# 9_FPGA_ADC_N.net
KiCad netlist of a schematic drawn in Altium Designer
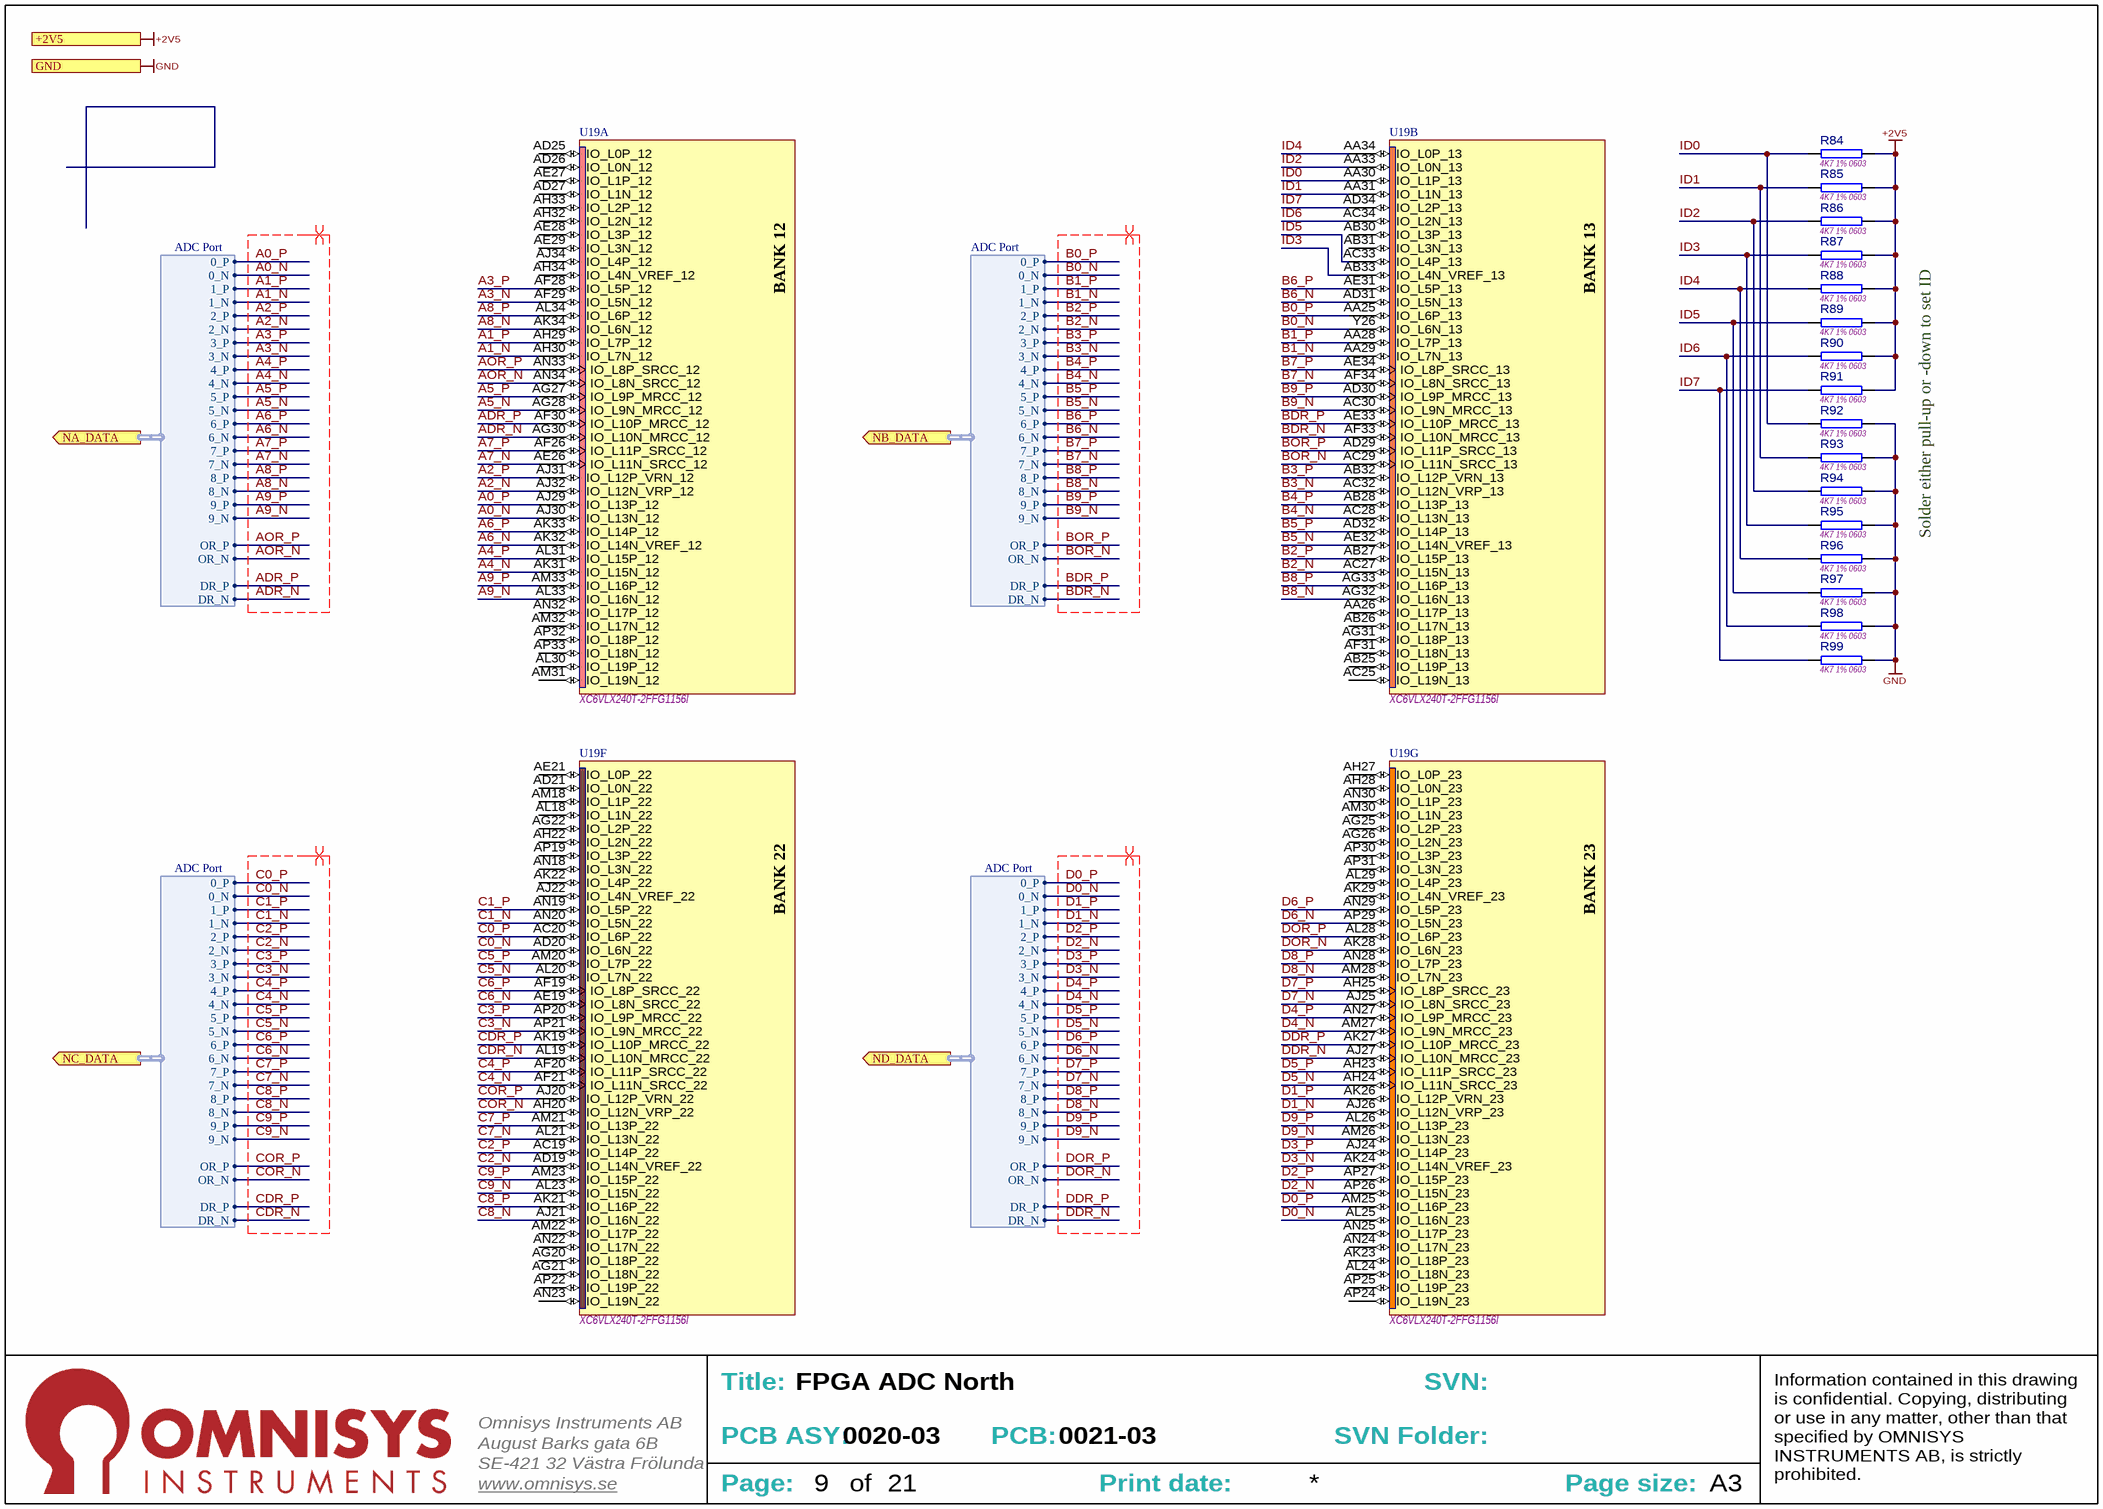
[diagram p0: [9] FPGA_ADC_N.SchDoc]

(export (version "E")
  (design (tool "Eeschema 10.0.6"))
  (components
    (comp (ref "R84")
      (value "4K7 1% 0603")
      (footprint "RESC1608N")
      (description "Thick film Chip Resistor, 0603/1608")
      (fields (field (name "POWER") "100mW") (field (name "TOLERANCE") "1%"))
      (libsource (lib "Omnisys Vault") (part "RES-2PIN"))
    )
    (comp (ref "R85")
      (value "4K7 1% 0603")
      (footprint "RESC1608N")
      (description "Thick film Chip Resistor, 0603/1608")
      (fields (field (name "POWER") "100mW") (field (name "TOLERANCE") "1%"))
      (libsource (lib "Omnisys Vault") (part "RES-2PIN"))
    )
    (comp (ref "R86")
      (value "4K7 1% 0603")
      (footprint "RESC1608N")
      (description "Thick film Chip Resistor, 0603/1608")
      (fields (field (name "POWER") "100mW") (field (name "TOLERANCE") "1%"))
      (libsource (lib "Omnisys Vault") (part "RES-2PIN"))
    )
    (comp (ref "R87")
      (value "4K7 1% 0603")
      (footprint "RESC1608N")
      (description "Thick film Chip Resistor, 0603/1608")
      (fields (field (name "POWER") "100mW") (field (name "TOLERANCE") "1%"))
      (libsource (lib "Omnisys Vault") (part "RES-2PIN"))
    )
    (comp (ref "R88")
      (value "4K7 1% 0603")
      (footprint "RESC1608N")
      (description "Thick film Chip Resistor, 0603/1608")
      (fields (field (name "POWER") "100mW") (field (name "TOLERANCE") "1%"))
      (libsource (lib "Omnisys Vault") (part "RES-2PIN"))
    )
    (comp (ref "R89")
      (value "4K7 1% 0603")
      (footprint "RESC1608N")
      (description "Thick film Chip Resistor, 0603/1608")
      (fields (field (name "POWER") "100mW") (field (name "TOLERANCE") "1%"))
      (libsource (lib "Omnisys Vault") (part "RES-2PIN"))
    )
    (comp (ref "R90")
      (value "4K7 1% 0603")
      (footprint "RESC1608N")
      (description "Thick film Chip Resistor, 0603/1608")
      (fields (field (name "POWER") "100mW") (field (name "TOLERANCE") "1%"))
      (libsource (lib "Omnisys Vault") (part "RES-2PIN"))
    )
    (comp (ref "R91")
      (value "4K7 1% 0603")
      (footprint "RESC1608N")
      (description "Thick film Chip Resistor, 0603/1608")
      (fields (field (name "POWER") "100mW") (field (name "TOLERANCE") "1%"))
      (libsource (lib "Omnisys Vault") (part "RES-2PIN"))
    )
    (comp (ref "R92")
      (value "4K7 1% 0603")
      (footprint "RESC1608N")
      (description "Thick film Chip Resistor, 0603/1608")
      (fields (field (name "POWER") "100mW") (field (name "TOLERANCE") "1%"))
      (libsource (lib "Omnisys Vault") (part "RES-2PIN"))
    )
    (comp (ref "R93")
      (value "4K7 1% 0603")
      (footprint "RESC1608N")
      (description "Thick film Chip Resistor, 0603/1608")
      (fields (field (name "POWER") "100mW") (field (name "TOLERANCE") "1%"))
      (libsource (lib "Omnisys Vault") (part "RES-2PIN"))
    )
    (comp (ref "R94")
      (value "4K7 1% 0603")
      (footprint "RESC1608N")
      (description "Thick film Chip Resistor, 0603/1608")
      (fields (field (name "POWER") "100mW") (field (name "TOLERANCE") "1%"))
      (libsource (lib "Omnisys Vault") (part "RES-2PIN"))
    )
    (comp (ref "R95")
      (value "4K7 1% 0603")
      (footprint "RESC1608N")
      (description "Thick film Chip Resistor, 0603/1608")
      (fields (field (name "POWER") "100mW") (field (name "TOLERANCE") "1%"))
      (libsource (lib "Omnisys Vault") (part "RES-2PIN"))
    )
    (comp (ref "R96")
      (value "4K7 1% 0603")
      (footprint "RESC1608N")
      (description "Thick film Chip Resistor, 0603/1608")
      (fields (field (name "POWER") "100mW") (field (name "TOLERANCE") "1%"))
      (libsource (lib "Omnisys Vault") (part "RES-2PIN"))
    )
    (comp (ref "R97")
      (value "4K7 1% 0603")
      (footprint "RESC1608N")
      (description "Thick film Chip Resistor, 0603/1608")
      (fields (field (name "POWER") "100mW") (field (name "TOLERANCE") "1%"))
      (libsource (lib "Omnisys Vault") (part "RES-2PIN"))
    )
    (comp (ref "R98")
      (value "4K7 1% 0603")
      (footprint "RESC1608N")
      (description "Thick film Chip Resistor, 0603/1608")
      (fields (field (name "POWER") "100mW") (field (name "TOLERANCE") "1%"))
      (libsource (lib "Omnisys Vault") (part "RES-2PIN"))
    )
    (comp (ref "R99")
      (value "4K7 1% 0603")
      (footprint "RESC1608N")
      (description "Thick film Chip Resistor, 0603/1608")
      (fields (field (name "POWER") "100mW") (field (name "TOLERANCE") "1%"))
      (libsource (lib "Omnisys Vault") (part "RES-2PIN"))
    )
    (comp (ref "U19")
      (value "XC6VLX240T-2FFG1156I")
      (footprint "FFG1156")
      (description "FPGA Virtex-6 LXT Family 241152 Cells 40nm (CMOS) Technology 1V 1156-Pin FCBGA")
      (libsource (lib "Omnisys Vault") (part "FPGA-XVR6-XC6VXXXXXT-GA1156"))
    )
  )
  (nets
    (net (code "3") (name "+2V5") (class "Default")
      (node (ref "R84") (pin "1") (pinfunction "1_1") (pintype "passive"))
      (node (ref "R85") (pin "1") (pinfunction "1_1") (pintype "passive"))
      (node (ref "R86") (pin "1") (pinfunction "1_1") (pintype "passive"))
      (node (ref "R87") (pin "1") (pinfunction "1_1") (pintype "passive"))
      (node (ref "R88") (pin "1") (pinfunction "1_1") (pintype "passive"))
      (node (ref "R89") (pin "1") (pinfunction "1_1") (pintype "passive"))
      (node (ref "R90") (pin "1") (pinfunction "1_1") (pintype "passive"))
      (node (ref "R91") (pin "1") (pinfunction "1_1") (pintype "passive"))
    )
    (net (code "4") (name "/A0_N") (class "Default")
      (node (ref "U19") (pin "AJ30") (pinfunction "IO_L13N_12_AJ30") (pintype "bidirectional"))
    )
    (net (code "5") (name "/A0_P") (class "Default")
      (node (ref "U19") (pin "AJ29") (pinfunction "IO_L13P_12_AJ29") (pintype "bidirectional"))
    )
    (net (code "6") (name "/A1_N") (class "Default")
      (node (ref "U19") (pin "AH30") (pinfunction "IO_L7N_12_AH30") (pintype "bidirectional"))
    )
    (net (code "7") (name "/A1_P") (class "Default")
      (node (ref "U19") (pin "AH29") (pinfunction "IO_L7P_12_AH29") (pintype "bidirectional"))
    )
    (net (code "8") (name "/A2_N") (class "Default")
      (node (ref "U19") (pin "AJ32") (pinfunction "IO_L12N_VRP_12_AJ32") (pintype "bidirectional"))
    )
    (net (code "9") (name "/A2_P") (class "Default")
      (node (ref "U19") (pin "AJ31") (pinfunction "IO_L12P_VRN_12_AJ31") (pintype "bidirectional"))
    )
    (net (code "10") (name "/A3_N") (class "Default")
      (node (ref "U19") (pin "AF29") (pinfunction "IO_L5N_12_AF29") (pintype "bidirectional"))
    )
    (net (code "11") (name "/A3_P") (class "Default")
      (node (ref "U19") (pin "AF28") (pinfunction "IO_L5P_12_AF28") (pintype "bidirectional"))
    )
    (net (code "12") (name "/A4_N") (class "Default")
      (node (ref "U19") (pin "AK31") (pinfunction "IO_L15N_12_AK31") (pintype "bidirectional"))
    )
    (net (code "13") (name "/A4_P") (class "Default")
      (node (ref "U19") (pin "AL31") (pinfunction "IO_L15P_12_AL31") (pintype "bidirectional"))
    )
    (net (code "14") (name "/A5_N") (class "Default")
      (node (ref "U19") (pin "AG28") (pinfunction "IO_L9N_MRCC_12_AG28") (pintype "bidirectional"))
    )
    (net (code "15") (name "/A5_P") (class "Default")
      (node (ref "U19") (pin "AG27") (pinfunction "IO_L9P_MRCC_12_AG27") (pintype "bidirectional"))
    )
    (net (code "16") (name "/A6_N") (class "Default")
      (node (ref "U19") (pin "AK32") (pinfunction "IO_L14N_VREF_12_AK32") (pintype "bidirectional"))
    )
    (net (code "17") (name "/A6_P") (class "Default")
      (node (ref "U19") (pin "AK33") (pinfunction "IO_L14P_12_AK33") (pintype "bidirectional"))
    )
    (net (code "18") (name "/A7_N") (class "Default")
      (node (ref "U19") (pin "AE26") (pinfunction "IO_L11N_SRCC_12_AE26") (pintype "bidirectional"))
    )
    (net (code "19") (name "/A7_P") (class "Default")
      (node (ref "U19") (pin "AF26") (pinfunction "IO_L11P_SRCC_12_AF26") (pintype "bidirectional"))
    )
    (net (code "20") (name "/A8_N") (class "Default")
      (node (ref "U19") (pin "AK34") (pinfunction "IO_L6N_12_AK34") (pintype "bidirectional"))
    )
    (net (code "21") (name "/A8_P") (class "Default")
      (node (ref "U19") (pin "AL34") (pinfunction "IO_L6P_12_AL34") (pintype "bidirectional"))
    )
    (net (code "22") (name "/A9_N") (class "Default")
      (node (ref "U19") (pin "AL33") (pinfunction "IO_L16N_12_AL33") (pintype "bidirectional"))
    )
    (net (code "23") (name "/A9_P") (class "Default")
      (node (ref "U19") (pin "AM33") (pinfunction "IO_L16P_12_AM33") (pintype "bidirectional"))
    )
    (net (code "24") (name "/ADR_N") (class "Default")
      (node (ref "U19") (pin "AG30") (pinfunction "IO_L10N_MRCC_12_AG30") (pintype "bidirectional"))
    )
    (net (code "25") (name "/ADR_P") (class "Default")
      (node (ref "U19") (pin "AF30") (pinfunction "IO_L10P_MRCC_12_AF30") (pintype "bidirectional"))
    )
    (net (code "26") (name "/AOR_N") (class "Default")
      (node (ref "U19") (pin "AN34") (pinfunction "IO_L8N_SRCC_12_AN34") (pintype "bidirectional"))
    )
    (net (code "27") (name "/AOR_P") (class "Default")
      (node (ref "U19") (pin "AN33") (pinfunction "IO_L8P_SRCC_12_AN33") (pintype "bidirectional"))
    )
    (net (code "28") (name "/B0_N") (class "Default")
      (node (ref "U19") (pin "Y26") (pinfunction "IO_L6N_13_Y26") (pintype "bidirectional"))
    )
    (net (code "29") (name "/B0_P") (class "Default")
      (node (ref "U19") (pin "AA25") (pinfunction "IO_L6P_13_AA25") (pintype "bidirectional"))
    )
    (net (code "30") (name "/B1_N") (class "Default")
      (node (ref "U19") (pin "AA29") (pinfunction "IO_L7N_13_AA29") (pintype "bidirectional"))
    )
    (net (code "31") (name "/B1_P") (class "Default")
      (node (ref "U19") (pin "AA28") (pinfunction "IO_L7P_13_AA28") (pintype "bidirectional"))
    )
    (net (code "32") (name "/B2_N") (class "Default")
      (node (ref "U19") (pin "AC27") (pinfunction "IO_L15N_13_AC27") (pintype "bidirectional"))
    )
    (net (code "33") (name "/B2_P") (class "Default")
      (node (ref "U19") (pin "AB27") (pinfunction "IO_L15P_13_AB27") (pintype "bidirectional"))
    )
    (net (code "34") (name "/B3_N") (class "Default")
      (node (ref "U19") (pin "AC32") (pinfunction "IO_L12N_VRP_13_AC32") (pintype "bidirectional"))
    )
    (net (code "35") (name "/B3_P") (class "Default")
      (node (ref "U19") (pin "AB32") (pinfunction "IO_L12P_VRN_13_AB32") (pintype "bidirectional"))
    )
    (net (code "36") (name "/B4_N") (class "Default")
      (node (ref "U19") (pin "AC28") (pinfunction "IO_L13N_13_AC28") (pintype "bidirectional"))
    )
    (net (code "37") (name "/B4_P") (class "Default")
      (node (ref "U19") (pin "AB28") (pinfunction "IO_L13P_13_AB28") (pintype "bidirectional"))
    )
    (net (code "38") (name "/B5_N") (class "Default")
      (node (ref "U19") (pin "AE32") (pinfunction "IO_L14N_VREF_13_AE32") (pintype "bidirectional"))
    )
    (net (code "39") (name "/B5_P") (class "Default")
      (node (ref "U19") (pin "AD32") (pinfunction "IO_L14P_13_AD32") (pintype "bidirectional"))
    )
    (net (code "40") (name "/B6_N") (class "Default")
      (node (ref "U19") (pin "AD31") (pinfunction "IO_L5N_13_AD31") (pintype "bidirectional"))
    )
    (net (code "41") (name "/B6_P") (class "Default")
      (node (ref "U19") (pin "AE31") (pinfunction "IO_L5P_13_AE31") (pintype "bidirectional"))
    )
    (net (code "42") (name "/B7_N") (class "Default")
      (node (ref "U19") (pin "AF34") (pinfunction "IO_L8N_SRCC_13_AF34") (pintype "bidirectional"))
    )
    (net (code "43") (name "/B7_P") (class "Default")
      (node (ref "U19") (pin "AE34") (pinfunction "IO_L8P_SRCC_13_AE34") (pintype "bidirectional"))
    )
    (net (code "44") (name "/B8_N") (class "Default")
      (node (ref "U19") (pin "AG32") (pinfunction "IO_L16N_13_AG32") (pintype "bidirectional"))
    )
    (net (code "45") (name "/B8_P") (class "Default")
      (node (ref "U19") (pin "AG33") (pinfunction "IO_L16P_13_AG33") (pintype "bidirectional"))
    )
    (net (code "46") (name "/B9_N") (class "Default")
      (node (ref "U19") (pin "AC30") (pinfunction "IO_L9N_MRCC_13_AC30") (pintype "bidirectional"))
    )
    (net (code "47") (name "/B9_P") (class "Default")
      (node (ref "U19") (pin "AD30") (pinfunction "IO_L9P_MRCC_13_AD30") (pintype "bidirectional"))
    )
    (net (code "48") (name "/BDR_N") (class "Default")
      (node (ref "U19") (pin "AF33") (pinfunction "IO_L10N_MRCC_13_AF33") (pintype "bidirectional"))
    )
    (net (code "49") (name "/BDR_P") (class "Default")
      (node (ref "U19") (pin "AE33") (pinfunction "IO_L10P_MRCC_13_AE33") (pintype "bidirectional"))
    )
    (net (code "50") (name "/BOR_N") (class "Default")
      (node (ref "U19") (pin "AC29") (pinfunction "IO_L11N_SRCC_13_AC29") (pintype "bidirectional"))
    )
    (net (code "51") (name "/BOR_P") (class "Default")
      (node (ref "U19") (pin "AD29") (pinfunction "IO_L11P_SRCC_13_AD29") (pintype "bidirectional"))
    )
    (net (code "52") (name "/C0_N") (class "Default")
      (node (ref "U19") (pin "AD20") (pinfunction "IO_L6N_22_AD20") (pintype "bidirectional"))
    )
    (net (code "53") (name "/C0_P") (class "Default")
      (node (ref "U19") (pin "AC20") (pinfunction "IO_L6P_22_AC20") (pintype "bidirectional"))
    )
    (net (code "54") (name "/C1_N") (class "Default")
      (node (ref "U19") (pin "AN20") (pinfunction "IO_L5N_22_AN20") (pintype "bidirectional"))
    )
    (net (code "55") (name "/C1_P") (class "Default")
      (node (ref "U19") (pin "AN19") (pinfunction "IO_L5P_22_AN19") (pintype "bidirectional"))
    )
    (net (code "56") (name "/C2_N") (class "Default")
      (node (ref "U19") (pin "AD19") (pinfunction "IO_L14N_VREF_22_AD19") (pintype "bidirectional"))
    )
    (net (code "57") (name "/C2_P") (class "Default")
      (node (ref "U19") (pin "AC19") (pinfunction "IO_L14P_22_AC19") (pintype "bidirectional"))
    )
    (net (code "58") (name "/C3_N") (class "Default")
      (node (ref "U19") (pin "AP21") (pinfunction "IO_L9N_MRCC_22_AP21") (pintype "bidirectional"))
    )
    (net (code "59") (name "/C3_P") (class "Default")
      (node (ref "U19") (pin "AP20") (pinfunction "IO_L9P_MRCC_22_AP20") (pintype "bidirectional"))
    )
    (net (code "60") (name "/C4_N") (class "Default")
      (node (ref "U19") (pin "AF21") (pinfunction "IO_L11N_SRCC_22_AF21") (pintype "bidirectional"))
    )
    (net (code "61") (name "/C4_P") (class "Default")
      (node (ref "U19") (pin "AF20") (pinfunction "IO_L11P_SRCC_22_AF20") (pintype "bidirectional"))
    )
    (net (code "62") (name "/C5_N") (class "Default")
      (node (ref "U19") (pin "AL20") (pinfunction "IO_L7N_22_AL20") (pintype "bidirectional"))
    )
    (net (code "63") (name "/C5_P") (class "Default")
      (node (ref "U19") (pin "AM20") (pinfunction "IO_L7P_22_AM20") (pintype "bidirectional"))
    )
    (net (code "64") (name "/C6_N") (class "Default")
      (node (ref "U19") (pin "AE19") (pinfunction "IO_L8N_SRCC_22_AE19") (pintype "bidirectional"))
    )
    (net (code "65") (name "/C6_P") (class "Default")
      (node (ref "U19") (pin "AF19") (pinfunction "IO_L8P_SRCC_22_AF19") (pintype "bidirectional"))
    )
    (net (code "66") (name "/C7_N") (class "Default")
      (node (ref "U19") (pin "AL21") (pinfunction "IO_L13N_22_AL21") (pintype "bidirectional"))
    )
    (net (code "67") (name "/C7_P") (class "Default")
      (node (ref "U19") (pin "AM21") (pinfunction "IO_L13P_22_AM21") (pintype "bidirectional"))
    )
    (net (code "68") (name "/C8_N") (class "Default")
      (node (ref "U19") (pin "AJ21") (pinfunction "IO_L16N_22_AJ21") (pintype "bidirectional"))
    )
    (net (code "69") (name "/C8_P") (class "Default")
      (node (ref "U19") (pin "AK21") (pinfunction "IO_L16P_22_AK21") (pintype "bidirectional"))
    )
    (net (code "70") (name "/C9_N") (class "Default")
      (node (ref "U19") (pin "AL23") (pinfunction "IO_L15N_22_AL23") (pintype "bidirectional"))
    )
    (net (code "71") (name "/C9_P") (class "Default")
      (node (ref "U19") (pin "AM23") (pinfunction "IO_L15P_22_AM23") (pintype "bidirectional"))
    )
    (net (code "72") (name "/CDR_N") (class "Default")
      (node (ref "U19") (pin "AL19") (pinfunction "IO_L10N_MRCC_22_AL19") (pintype "bidirectional"))
    )
    (net (code "73") (name "/CDR_P") (class "Default")
      (node (ref "U19") (pin "AK19") (pinfunction "IO_L10P_MRCC_22_AK19") (pintype "bidirectional"))
    )
    (net (code "74") (name "/COR_N") (class "Default")
      (node (ref "U19") (pin "AH20") (pinfunction "IO_L12N_VRP_22_AH20") (pintype "bidirectional"))
    )
    (net (code "75") (name "/COR_P") (class "Default")
      (node (ref "U19") (pin "AJ20") (pinfunction "IO_L12P_VRN_22_AJ20") (pintype "bidirectional"))
    )
    (net (code "76") (name "/D0_N") (class "Default")
      (node (ref "U19") (pin "AL25") (pinfunction "IO_L16N_23_AL25") (pintype "bidirectional"))
    )
    (net (code "77") (name "/D0_P") (class "Default")
      (node (ref "U19") (pin "AM25") (pinfunction "IO_L16P_23_AM25") (pintype "bidirectional"))
    )
    (net (code "78") (name "/D1_N") (class "Default")
      (node (ref "U19") (pin "AJ26") (pinfunction "IO_L12N_VRP_23_AJ26") (pintype "bidirectional"))
    )
    (net (code "79") (name "/D1_P") (class "Default")
      (node (ref "U19") (pin "AK26") (pinfunction "IO_L12P_VRN_23_AK26") (pintype "bidirectional"))
    )
    (net (code "80") (name "/D2_N") (class "Default")
      (node (ref "U19") (pin "AP26") (pinfunction "IO_L15N_23_AP26") (pintype "bidirectional"))
    )
    (net (code "81") (name "/D2_P") (class "Default")
      (node (ref "U19") (pin "AP27") (pinfunction "IO_L15P_23_AP27") (pintype "bidirectional"))
    )
    (net (code "82") (name "/D3_N") (class "Default")
      (node (ref "U19") (pin "AK24") (pinfunction "IO_L14N_VREF_23_AK24") (pintype "bidirectional"))
    )
    (net (code "83") (name "/D3_P") (class "Default")
      (node (ref "U19") (pin "AJ24") (pinfunction "IO_L14P_23_AJ24") (pintype "bidirectional"))
    )
    (net (code "84") (name "/D4_N") (class "Default")
      (node (ref "U19") (pin "AM27") (pinfunction "IO_L9N_MRCC_23_AM27") (pintype "bidirectional"))
    )
    (net (code "85") (name "/D4_P") (class "Default")
      (node (ref "U19") (pin "AN27") (pinfunction "IO_L9P_MRCC_23_AN27") (pintype "bidirectional"))
    )
    (net (code "86") (name "/D5_N") (class "Default")
      (node (ref "U19") (pin "AH24") (pinfunction "IO_L11N_SRCC_23_AH24") (pintype "bidirectional"))
    )
    (net (code "87") (name "/D5_P") (class "Default")
      (node (ref "U19") (pin "AH23") (pinfunction "IO_L11P_SRCC_23_AH23") (pintype "bidirectional"))
    )
    (net (code "88") (name "/D6_N") (class "Default")
      (node (ref "U19") (pin "AP29") (pinfunction "IO_L5N_23_AP29") (pintype "bidirectional"))
    )
    (net (code "89") (name "/D6_P") (class "Default")
      (node (ref "U19") (pin "AN29") (pinfunction "IO_L5P_23_AN29") (pintype "bidirectional"))
    )
    (net (code "90") (name "/D7_N") (class "Default")
      (node (ref "U19") (pin "AJ25") (pinfunction "IO_L8N_SRCC_23_AJ25") (pintype "bidirectional"))
    )
    (net (code "91") (name "/D7_P") (class "Default")
      (node (ref "U19") (pin "AH25") (pinfunction "IO_L8P_SRCC_23_AH25") (pintype "bidirectional"))
    )
    (net (code "92") (name "/D8_N") (class "Default")
      (node (ref "U19") (pin "AM28") (pinfunction "IO_L7N_23_AM28") (pintype "bidirectional"))
    )
    (net (code "93") (name "/D8_P") (class "Default")
      (node (ref "U19") (pin "AN28") (pinfunction "IO_L7P_23_AN28") (pintype "bidirectional"))
    )
    (net (code "94") (name "/D9_N") (class "Default")
      (node (ref "U19") (pin "AM26") (pinfunction "IO_L13N_23_AM26") (pintype "bidirectional"))
    )
    (net (code "95") (name "/D9_P") (class "Default")
      (node (ref "U19") (pin "AL26") (pinfunction "IO_L13P_23_AL26") (pintype "bidirectional"))
    )
    (net (code "96") (name "/DDR_N") (class "Default")
      (node (ref "U19") (pin "AJ27") (pinfunction "IO_L10N_MRCC_23_AJ27") (pintype "bidirectional"))
    )
    (net (code "97") (name "/DDR_P") (class "Default")
      (node (ref "U19") (pin "AK27") (pinfunction "IO_L10P_MRCC_23_AK27") (pintype "bidirectional"))
    )
    (net (code "98") (name "/DOR_N") (class "Default")
      (node (ref "U19") (pin "AK28") (pinfunction "IO_L6N_23_AK28") (pintype "bidirectional"))
    )
    (net (code "99") (name "/DOR_P") (class "Default")
      (node (ref "U19") (pin "AL28") (pinfunction "IO_L6P_23_AL28") (pintype "bidirectional"))
    )
    (net (code "100") (name "/ID0") (class "Default")
      (node (ref "R84") (pin "2") (pinfunction "2_2") (pintype "passive"))
      (node (ref "R92") (pin "2") (pinfunction "2_2") (pintype "passive"))
      (node (ref "U19") (pin "AA30") (pinfunction "IO_L1P_13_AA30") (pintype "bidirectional"))
    )
    (net (code "101") (name "/ID1") (class "Default")
      (node (ref "R85") (pin "2") (pinfunction "2_2") (pintype "passive"))
      (node (ref "R93") (pin "2") (pinfunction "2_2") (pintype "passive"))
      (node (ref "U19") (pin "AA31") (pinfunction "IO_L1N_13_AA31") (pintype "bidirectional"))
    )
    (net (code "102") (name "/ID2") (class "Default")
      (node (ref "R86") (pin "2") (pinfunction "2_2") (pintype "passive"))
      (node (ref "R94") (pin "2") (pinfunction "2_2") (pintype "passive"))
      (node (ref "U19") (pin "AA33") (pinfunction "IO_L0N_13_AA33") (pintype "bidirectional"))
    )
    (net (code "103") (name "/ID3") (class "Default")
      (node (ref "R87") (pin "2") (pinfunction "2_2") (pintype "passive"))
      (node (ref "R95") (pin "2") (pinfunction "2_2") (pintype "passive"))
      (node (ref "U19") (pin "AB33") (pinfunction "IO_L4N_VREF_13_AB33") (pintype "bidirectional"))
    )
    (net (code "104") (name "/ID4") (class "Default")
      (node (ref "R88") (pin "2") (pinfunction "2_2") (pintype "passive"))
      (node (ref "R96") (pin "2") (pinfunction "2_2") (pintype "passive"))
      (node (ref "U19") (pin "AA34") (pinfunction "IO_L0P_13_AA34") (pintype "bidirectional"))
    )
    (net (code "105") (name "/ID5") (class "Default")
      (node (ref "R89") (pin "2") (pinfunction "2_2") (pintype "passive"))
      (node (ref "R97") (pin "2") (pinfunction "2_2") (pintype "passive"))
      (node (ref "U19") (pin "AC33") (pinfunction "IO_L4P_13_AC33") (pintype "bidirectional"))
    )
    (net (code "106") (name "/ID6") (class "Default")
      (node (ref "R90") (pin "2") (pinfunction "2_2") (pintype "passive"))
      (node (ref "R98") (pin "2") (pinfunction "2_2") (pintype "passive"))
      (node (ref "U19") (pin "AC34") (pinfunction "IO_L2N_13_AC34") (pintype "bidirectional"))
    )
    (net (code "107") (name "/ID7") (class "Default")
      (node (ref "R91") (pin "2") (pinfunction "2_2") (pintype "passive"))
      (node (ref "R99") (pin "2") (pinfunction "2_2") (pintype "passive"))
      (node (ref "U19") (pin "AD34") (pinfunction "IO_L2P_13_AD34") (pintype "bidirectional"))
    )
    (net (code "109") (name "GND") (class "Default")
      (node (ref "R92") (pin "1") (pinfunction "1_1") (pintype "passive"))
      (node (ref "R93") (pin "1") (pinfunction "1_1") (pintype "passive"))
      (node (ref "R94") (pin "1") (pinfunction "1_1") (pintype "passive"))
      (node (ref "R95") (pin "1") (pinfunction "1_1") (pintype "passive"))
      (node (ref "R96") (pin "1") (pinfunction "1_1") (pintype "passive"))
      (node (ref "R97") (pin "1") (pinfunction "1_1") (pintype "passive"))
      (node (ref "R98") (pin "1") (pinfunction "1_1") (pintype "passive"))
      (node (ref "R99") (pin "1") (pinfunction "1_1") (pintype "passive"))
    )
    (net (code "110") (name "unconnected-(U19A-IO_L0N_12-PadAD26)") (class "Default")
      (node (ref "U19") (pin "AD26") (pinfunction "IO_L0N_12_AD26") (pintype "bidirectional"))
    )
    (net (code "111") (name "unconnected-(U19A-IO_L0P_12-PadAD25)") (class "Default")
      (node (ref "U19") (pin "AD25") (pinfunction "IO_L0P_12_AD25") (pintype "bidirectional"))
    )
    (net (code "112") (name "unconnected-(U19A-IO_L1N_12-PadAD27)") (class "Default")
      (node (ref "U19") (pin "AD27") (pinfunction "IO_L1N_12_AD27") (pintype "bidirectional"))
    )
    (net (code "113") (name "unconnected-(U19A-IO_L1P_12-PadAE27)") (class "Default")
      (node (ref "U19") (pin "AE27") (pinfunction "IO_L1P_12_AE27") (pintype "bidirectional"))
    )
    (net (code "114") (name "unconnected-(U19A-IO_L2N_12-PadAH32)") (class "Default")
      (node (ref "U19") (pin "AH32") (pinfunction "IO_L2N_12_AH32") (pintype "bidirectional"))
    )
    (net (code "115") (name "unconnected-(U19A-IO_L2P_12-PadAH33)") (class "Default")
      (node (ref "U19") (pin "AH33") (pinfunction "IO_L2P_12_AH33") (pintype "bidirectional"))
    )
    (net (code "116") (name "unconnected-(U19A-IO_L3N_12-PadAE29)") (class "Default")
      (node (ref "U19") (pin "AE29") (pinfunction "IO_L3N_12_AE29") (pintype "bidirectional"))
    )
    (net (code "117") (name "unconnected-(U19A-IO_L3P_12-PadAE28)") (class "Default")
      (node (ref "U19") (pin "AE28") (pinfunction "IO_L3P_12_AE28") (pintype "bidirectional"))
    )
    (net (code "118") (name "unconnected-(U19A-IO_L4N_VREF_12-PadAH34)") (class "Default")
      (node (ref "U19") (pin "AH34") (pinfunction "IO_L4N_VREF_12_AH34") (pintype "bidirectional"))
    )
    (net (code "119") (name "unconnected-(U19A-IO_L4P_12-PadAJ34)") (class "Default")
      (node (ref "U19") (pin "AJ34") (pinfunction "IO_L4P_12_AJ34") (pintype "bidirectional"))
    )
    (net (code "120") (name "unconnected-(U19A-IO_L17N_12-PadAM32)") (class "Default")
      (node (ref "U19") (pin "AM32") (pinfunction "IO_L17N_12_AM32") (pintype "bidirectional"))
    )
    (net (code "121") (name "unconnected-(U19A-IO_L17P_12-PadAN32)") (class "Default")
      (node (ref "U19") (pin "AN32") (pinfunction "IO_L17P_12_AN32") (pintype "bidirectional"))
    )
    (net (code "122") (name "unconnected-(U19A-IO_L18N_12-PadAP33)") (class "Default")
      (node (ref "U19") (pin "AP33") (pinfunction "IO_L18N_12_AP33") (pintype "bidirectional"))
    )
    (net (code "123") (name "unconnected-(U19A-IO_L18P_12-PadAP32)") (class "Default")
      (node (ref "U19") (pin "AP32") (pinfunction "IO_L18P_12_AP32") (pintype "bidirectional"))
    )
    (net (code "124") (name "unconnected-(U19A-IO_L19N_12-PadAM31)") (class "Default")
      (node (ref "U19") (pin "AM31") (pinfunction "IO_L19N_12_AM31") (pintype "bidirectional"))
    )
    (net (code "125") (name "unconnected-(U19A-IO_L19P_12-PadAL30)") (class "Default")
      (node (ref "U19") (pin "AL30") (pinfunction "IO_L19P_12_AL30") (pintype "bidirectional"))
    )
    (net (code "126") (name "unconnected-(U19B-IO_L3N_13-PadAB31)") (class "Default")
      (node (ref "U19") (pin "AB31") (pinfunction "IO_L3N_13_AB31") (pintype "bidirectional"))
    )
    (net (code "127") (name "unconnected-(U19B-IO_L3P_13-PadAB30)") (class "Default")
      (node (ref "U19") (pin "AB30") (pinfunction "IO_L3P_13_AB30") (pintype "bidirectional"))
    )
    (net (code "128") (name "unconnected-(U19B-IO_L17N_13-PadAB26)") (class "Default")
      (node (ref "U19") (pin "AB26") (pinfunction "IO_L17N_13_AB26") (pintype "bidirectional"))
    )
    (net (code "129") (name "unconnected-(U19B-IO_L17P_13-PadAA26)") (class "Default")
      (node (ref "U19") (pin "AA26") (pinfunction "IO_L17P_13_AA26") (pintype "bidirectional"))
    )
    (net (code "130") (name "unconnected-(U19B-IO_L18N_13-PadAF31)") (class "Default")
      (node (ref "U19") (pin "AF31") (pinfunction "IO_L18N_13_AF31") (pintype "bidirectional"))
    )
    (net (code "131") (name "unconnected-(U19B-IO_L18P_13-PadAG31)") (class "Default")
      (node (ref "U19") (pin "AG31") (pinfunction "IO_L18P_13_AG31") (pintype "bidirectional"))
    )
    (net (code "132") (name "unconnected-(U19B-IO_L19N_13-PadAC25)") (class "Default")
      (node (ref "U19") (pin "AC25") (pinfunction "IO_L19N_13_AC25") (pintype "bidirectional"))
    )
    (net (code "133") (name "unconnected-(U19B-IO_L19P_13-PadAB25)") (class "Default")
      (node (ref "U19") (pin "AB25") (pinfunction "IO_L19P_13_AB25") (pintype "bidirectional"))
    )
    (net (code "134") (name "unconnected-(U19F-IO_L0N_22-PadAD21)") (class "Default")
      (node (ref "U19") (pin "AD21") (pinfunction "IO_L0N_22_AD21") (pintype "bidirectional"))
    )
    (net (code "135") (name "unconnected-(U19F-IO_L0P_22-PadAE21)") (class "Default")
      (node (ref "U19") (pin "AE21") (pinfunction "IO_L0P_22_AE21") (pintype "bidirectional"))
    )
    (net (code "136") (name "unconnected-(U19F-IO_L1N_22-PadAL18)") (class "Default")
      (node (ref "U19") (pin "AL18") (pinfunction "IO_L1N_22_AL18") (pintype "bidirectional"))
    )
    (net (code "137") (name "unconnected-(U19F-IO_L1P_22-PadAM18)") (class "Default")
      (node (ref "U19") (pin "AM18") (pinfunction "IO_L1P_22_AM18") (pintype "bidirectional"))
    )
    (net (code "138") (name "unconnected-(U19F-IO_L2N_22-PadAH22)") (class "Default")
      (node (ref "U19") (pin "AH22") (pinfunction "IO_L2N_22_AH22") (pintype "bidirectional"))
    )
    (net (code "139") (name "unconnected-(U19F-IO_L2P_22-PadAG22)") (class "Default")
      (node (ref "U19") (pin "AG22") (pinfunction "IO_L2P_22_AG22") (pintype "bidirectional"))
    )
    (net (code "140") (name "unconnected-(U19F-IO_L3N_22-PadAN18)") (class "Default")
      (node (ref "U19") (pin "AN18") (pinfunction "IO_L3N_22_AN18") (pintype "bidirectional"))
    )
    (net (code "141") (name "unconnected-(U19F-IO_L3P_22-PadAP19)") (class "Default")
      (node (ref "U19") (pin "AP19") (pinfunction "IO_L3P_22_AP19") (pintype "bidirectional"))
    )
    (net (code "142") (name "unconnected-(U19F-IO_L4N_VREF_22-PadAJ22)") (class "Default")
      (node (ref "U19") (pin "AJ22") (pinfunction "IO_L4N_VREF_22_AJ22") (pintype "bidirectional"))
    )
    (net (code "143") (name "unconnected-(U19F-IO_L4P_22-PadAK22)") (class "Default")
      (node (ref "U19") (pin "AK22") (pinfunction "IO_L4P_22_AK22") (pintype "bidirectional"))
    )
    (net (code "144") (name "unconnected-(U19F-IO_L17N_22-PadAN22)") (class "Default")
      (node (ref "U19") (pin "AN22") (pinfunction "IO_L17N_22_AN22") (pintype "bidirectional"))
    )
    (net (code "145") (name "unconnected-(U19F-IO_L17P_22-PadAM22)") (class "Default")
      (node (ref "U19") (pin "AM22") (pinfunction "IO_L17P_22_AM22") (pintype "bidirectional"))
    )
    (net (code "146") (name "unconnected-(U19F-IO_L18N_22-PadAG21)") (class "Default")
      (node (ref "U19") (pin "AG21") (pinfunction "IO_L18N_22_AG21") (pintype "bidirectional"))
    )
    (net (code "147") (name "unconnected-(U19F-IO_L18P_22-PadAG20)") (class "Default")
      (node (ref "U19") (pin "AG20") (pinfunction "IO_L18P_22_AG20") (pintype "bidirectional"))
    )
    (net (code "148") (name "unconnected-(U19F-IO_L19N_22-PadAN23)") (class "Default")
      (node (ref "U19") (pin "AN23") (pinfunction "IO_L19N_22_AN23") (pintype "bidirectional"))
    )
    (net (code "149") (name "unconnected-(U19F-IO_L19P_22-PadAP22)") (class "Default")
      (node (ref "U19") (pin "AP22") (pinfunction "IO_L19P_22_AP22") (pintype "bidirectional"))
    )
    (net (code "150") (name "unconnected-(U19G-IO_L0N_23-PadAH28)") (class "Default")
      (node (ref "U19") (pin "AH28") (pinfunction "IO_L0N_23_AH28") (pintype "bidirectional"))
    )
    (net (code "151") (name "unconnected-(U19G-IO_L0P_23-PadAH27)") (class "Default")
      (node (ref "U19") (pin "AH27") (pinfunction "IO_L0P_23_AH27") (pintype "bidirectional"))
    )
    (net (code "152") (name "unconnected-(U19G-IO_L1N_23-PadAM30)") (class "Default")
      (node (ref "U19") (pin "AM30") (pinfunction "IO_L1N_23_AM30") (pintype "bidirectional"))
    )
    (net (code "153") (name "unconnected-(U19G-IO_L1P_23-PadAN30)") (class "Default")
      (node (ref "U19") (pin "AN30") (pinfunction "IO_L1P_23_AN30") (pintype "bidirectional"))
    )
    (net (code "154") (name "unconnected-(U19G-IO_L2N_23-PadAG26)") (class "Default")
      (node (ref "U19") (pin "AG26") (pinfunction "IO_L2N_23_AG26") (pintype "bidirectional"))
    )
    (net (code "155") (name "unconnected-(U19G-IO_L2P_23-PadAG25)") (class "Default")
      (node (ref "U19") (pin "AG25") (pinfunction "IO_L2P_23_AG25") (pintype "bidirectional"))
    )
    (net (code "156") (name "unconnected-(U19G-IO_L3N_23-PadAP31)") (class "Default")
      (node (ref "U19") (pin "AP31") (pinfunction "IO_L3N_23_AP31") (pintype "bidirectional"))
    )
    (net (code "157") (name "unconnected-(U19G-IO_L3P_23-PadAP30)") (class "Default")
      (node (ref "U19") (pin "AP30") (pinfunction "IO_L3P_23_AP30") (pintype "bidirectional"))
    )
    (net (code "158") (name "unconnected-(U19G-IO_L4N_VREF_23-PadAK29)") (class "Default")
      (node (ref "U19") (pin "AK29") (pinfunction "IO_L4N_VREF_23_AK29") (pintype "bidirectional"))
    )
    (net (code "159") (name "unconnected-(U19G-IO_L4P_23-PadAL29)") (class "Default")
      (node (ref "U19") (pin "AL29") (pinfunction "IO_L4P_23_AL29") (pintype "bidirectional"))
    )
    (net (code "160") (name "unconnected-(U19G-IO_L17N_23-PadAN24)") (class "Default")
      (node (ref "U19") (pin "AN24") (pinfunction "IO_L17N_23_AN24") (pintype "bidirectional"))
    )
    (net (code "161") (name "unconnected-(U19G-IO_L17P_23-PadAN25)") (class "Default")
      (node (ref "U19") (pin "AN25") (pinfunction "IO_L17P_23_AN25") (pintype "bidirectional"))
    )
    (net (code "162") (name "unconnected-(U19G-IO_L18N_23-PadAL24)") (class "Default")
      (node (ref "U19") (pin "AL24") (pinfunction "IO_L18N_23_AL24") (pintype "bidirectional"))
    )
    (net (code "163") (name "unconnected-(U19G-IO_L18P_23-PadAK23)") (class "Default")
      (node (ref "U19") (pin "AK23") (pinfunction "IO_L18P_23_AK23") (pintype "bidirectional"))
    )
    (net (code "164") (name "unconnected-(U19G-IO_L19N_23-PadAP24)") (class "Default")
      (node (ref "U19") (pin "AP24") (pinfunction "IO_L19N_23_AP24") (pintype "bidirectional"))
    )
    (net (code "165") (name "unconnected-(U19G-IO_L19P_23-PadAP25)") (class "Default")
      (node (ref "U19") (pin "AP25") (pinfunction "IO_L19P_23_AP25") (pintype "bidirectional"))
    )
  )
)
